# 08-STM32-01.net
KiCad netlist of a schematic drawn in Altium Designer
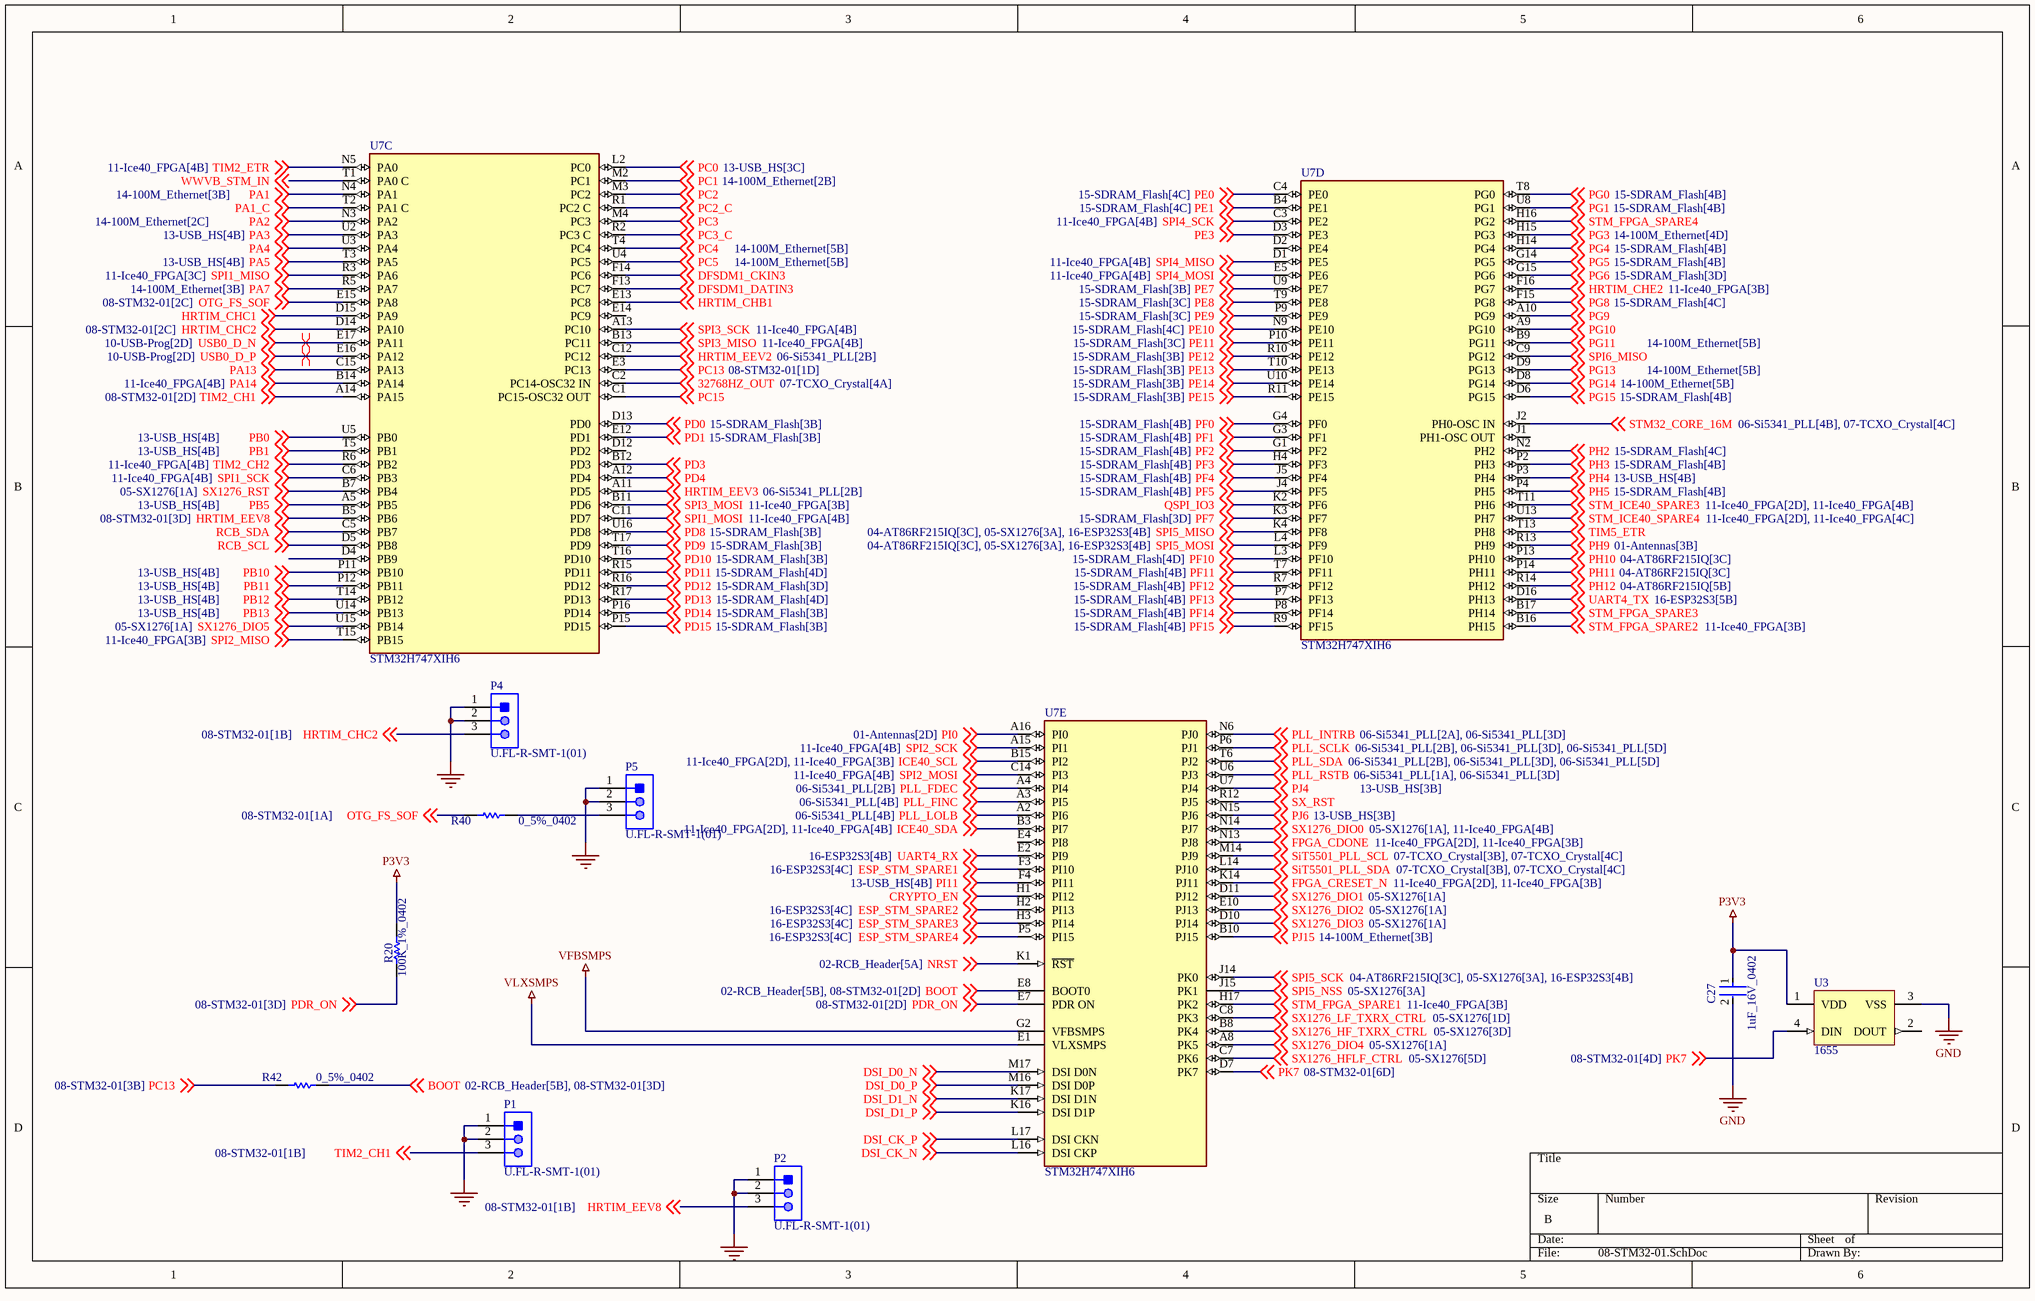
[diagram p0: 08-STM32-01.SchDoc]

(export (version "E")
  (design (tool "Eeschema 10.0.6"))
  (components
    (comp (ref "C27")
      (value "1uF_16V_0402")
      (footprint "FP-0402-L_1_0_0_05-W_0_5-IPC_A")
      (description "None")
      (fields (field (name "TOLERANCE") "10%"))
      (libsource (lib "Altium Content Vault") (part "b4654b650e69147ec39a6b967a45e02"))
    )
    (comp (ref "P1")
      (value "U.FL-R-SMT-1(01)")
      (footprint "HRS-U.FL-R-SMT-3_V")
      (description "Ultra Small Coaxial Connector, 6 GHz, -40 to 90 degC, 3-Pin SMD, RoHS, Bulk")
      (fields (field (name "MANUFACTURER") "Hirose Electric"))
      (libsource (lib "Altium Content Vault") (part "CN-1P-M-R3"))
    )
    (comp (ref "P2")
      (value "U.FL-R-SMT-1(01)")
      (footprint "HRS-U.FL-R-SMT-3_V")
      (description "Ultra Small Coaxial Connector, 6 GHz, -40 to 90 degC, 3-Pin SMD, RoHS, Bulk")
      (fields (field (name "MANUFACTURER") "Hirose Electric"))
      (libsource (lib "Altium Content Vault") (part "CN-1P-M-R3"))
    )
    (comp (ref "P4")
      (value "U.FL-R-SMT-1(01)")
      (footprint "HRS-U.FL-R-SMT-3_V")
      (description "Ultra Small Coaxial Connector, 6 GHz, -40 to 90 degC, 3-Pin SMD, RoHS, Bulk")
      (fields (field (name "MANUFACTURER") "Hirose Electric"))
      (libsource (lib "Altium Content Vault") (part "CN-1P-M-R3"))
    )
    (comp (ref "P5")
      (value "U.FL-R-SMT-1(01)")
      (footprint "HRS-U.FL-R-SMT-3_V")
      (description "Ultra Small Coaxial Connector, 6 GHz, -40 to 90 degC, 3-Pin SMD, RoHS, Bulk")
      (fields (field (name "MANUFACTURER") "Hirose Electric"))
      (libsource (lib "Altium Content Vault") (part "CN-1P-M-R3"))
    )
    (comp (ref "R20")
      (value "100K_1%_0402")
      (footprint "RESC1005X40X25ML05T10")
      (fields (field (name "MANUFACTURER") "Yageo") (field (name "PART NUMBER") "RC0402FR-13100KL"))
      (libsource (lib "Altium Content Vault") (part "RES"))
    )
    (comp (ref "R40")
      (value "0_5%_0402")
      (footprint "RESC1005X40X25NL05T10")
      (fields (field (name "MANUFACTURER") "Panasonic") (field (name "PART NUMBER") "ERJ-U020R00X"))
      (libsource (lib "Altium Content Vault") (part "RES"))
    )
    (comp (ref "R42")
      (value "0_5%_0402")
      (footprint "RESC1005X40X25NL05T10")
      (fields (field (name "MANUFACTURER") "Panasonic") (field (name "PART NUMBER") "ERJ-U020R00X"))
      (libsource (lib "Altium Content Vault") (part "RES"))
    )
    (comp (ref "U3")
      (value "1655")
      (footprint "ADA-RGB-1655_V")
      (fields (field (name "MANUFACTURER") "Adafruit-Industries-LLC"))
      (libsource (lib "Altium Content Vault") (part "ADA-RGB-1655-4"))
    )
    (comp (ref "U7")
      (value "STM32H747XIH6")
      (footprint "FP-TFBGA240+25-A07U-MFG")
      (description "HIGH-PERFORMANCE AND DSP WITH DP")
      (fields
        (field (name "MANUFACTURER") "STMicroelectronics")
        (field (name "OCTOPART") "https://octopart.com/stm32h747xih6-stmicroelectronics-100293943")
      )
      (libsource (lib "Altium Content Vault") (part "41f839bdfd00d9510c8672f0f410bfb"))
    )
  )
  (nets
    (net (code "1") (name "32768HZ_OUT") (class "Default")
      (node (ref "U7") (pin "C2") (pinfunction "PC14-OSC32_IN_C2") (pintype "bidirectional"))
    )
    (net (code "2") (name "BOOT") (class "Default")
      (node (ref "R42") (pin "2") (pinfunction "2_2") (pintype "passive"))
      (node (ref "U7") (pin "E8") (pinfunction "BOOT0_E8") (pintype "passive"))
    )
    (net (code "3") (name "CRYPTO_EN") (class "Default")
      (node (ref "U7") (pin "H1") (pinfunction "PI12_H1") (pintype "bidirectional"))
    )
    (net (code "4") (name "DFSDM1_CKIN3") (class "Default")
      (node (ref "U7") (pin "F14") (pinfunction "PC6_F14") (pintype "bidirectional"))
    )
    (net (code "5") (name "DFSDM1_DATIN3") (class "Default")
      (node (ref "U7") (pin "F13") (pinfunction "PC7_F13") (pintype "bidirectional"))
    )
    (net (code "6") (name "DSI_CK_N") (class "Default")
      (node (ref "U7") (pin "L16") (pinfunction "DSI_CKP_L16") (pintype "input"))
    )
    (net (code "7") (name "DSI_CK_P") (class "Default")
      (node (ref "U7") (pin "L17") (pinfunction "DSI_CKN_L17") (pintype "input"))
    )
    (net (code "8") (name "DSI_D0_N") (class "Default")
      (node (ref "U7") (pin "M17") (pinfunction "DSI_D0N_M17") (pintype "input"))
    )
    (net (code "9") (name "DSI_D0_P") (class "Default")
      (node (ref "U7") (pin "M16") (pinfunction "DSI_D0P_M16") (pintype "input"))
    )
    (net (code "10") (name "DSI_D1_N") (class "Default")
      (node (ref "U7") (pin "K17") (pinfunction "DSI_D1N_K17") (pintype "input"))
    )
    (net (code "11") (name "DSI_D1_P") (class "Default")
      (node (ref "U7") (pin "K16") (pinfunction "DSI_D1P_K16") (pintype "input"))
    )
    (net (code "12") (name "ESP_STM_SPARE1") (class "Default")
      (node (ref "U7") (pin "F3") (pinfunction "PI10_F3") (pintype "bidirectional"))
    )
    (net (code "13") (name "ESP_STM_SPARE2") (class "Default")
      (node (ref "U7") (pin "H2") (pinfunction "PI13_H2") (pintype "bidirectional"))
    )
    (net (code "14") (name "ESP_STM_SPARE3") (class "Default")
      (node (ref "U7") (pin "H3") (pinfunction "PI14_H3") (pintype "bidirectional"))
    )
    (net (code "15") (name "ESP_STM_SPARE4") (class "Default")
      (node (ref "U7") (pin "P5") (pinfunction "PI15_P5") (pintype "bidirectional"))
    )
    (net (code "16") (name "FPGA_CDONE") (class "Default")
      (node (ref "U7") (pin "N13") (pinfunction "PJ8_N13") (pintype "bidirectional"))
    )
    (net (code "17") (name "FPGA_CRESET_N") (class "Default")
      (node (ref "U7") (pin "K14") (pinfunction "PJ11_K14") (pintype "bidirectional"))
    )
    (net (code "18") (name "GND") (class "Default")
      (node (ref "C27") (pin "2") (pinfunction "2_2") (pintype "passive"))
      (node (ref "P1") (pin "1") (pinfunction "1_1") (pintype "passive"))
      (node (ref "P1") (pin "2") (pinfunction "2_2") (pintype "passive"))
      (node (ref "P2") (pin "1") (pinfunction "1_1") (pintype "passive"))
      (node (ref "P2") (pin "2") (pinfunction "2_2") (pintype "passive"))
      (node (ref "P4") (pin "1") (pinfunction "1_1") (pintype "passive"))
      (node (ref "P4") (pin "2") (pinfunction "2_2") (pintype "passive"))
      (node (ref "P5") (pin "1") (pinfunction "1_1") (pintype "passive"))
      (node (ref "P5") (pin "2") (pinfunction "2_2") (pintype "passive"))
      (node (ref "U3") (pin "3") (pinfunction "VSS_3") (pintype "power_in"))
    )
    (net (code "19") (name "HRTIM_CHB1") (class "Default")
      (node (ref "U7") (pin "E13") (pinfunction "PC8_E13") (pintype "bidirectional"))
    )
    (net (code "20") (name "HRTIM_CHC1") (class "Default")
      (node (ref "U7") (pin "D15") (pinfunction "PA9_D15") (pintype "bidirectional"))
    )
    (net (code "21") (name "HRTIM_CHC2") (class "Default")
      (node (ref "P4") (pin "3") (pinfunction "3_3") (pintype "passive"))
      (node (ref "U7") (pin "D14") (pinfunction "PA10_D14") (pintype "bidirectional"))
    )
    (net (code "22") (name "HRTIM_CHE2") (class "Default")
      (node (ref "U7") (pin "F16") (pinfunction "PG7_F16") (pintype "bidirectional"))
    )
    (net (code "23") (name "HRTIM_EEV2") (class "Default")
      (node (ref "U7") (pin "C12") (pinfunction "PC12_C12") (pintype "bidirectional"))
    )
    (net (code "24") (name "HRTIM_EEV3") (class "Default")
      (node (ref "U7") (pin "A11") (pinfunction "PD5_A11") (pintype "bidirectional"))
    )
    (net (code "25") (name "HRTIM_EEV8") (class "Default")
      (node (ref "P2") (pin "3") (pinfunction "3_3") (pintype "passive"))
      (node (ref "U7") (pin "B5") (pinfunction "PB6_B5") (pintype "bidirectional"))
    )
    (net (code "26") (name "ICE40_SCL") (class "Default")
      (node (ref "U7") (pin "B15") (pinfunction "PI2_B15") (pintype "bidirectional"))
    )
    (net (code "27") (name "ICE40_SDA") (class "Default")
      (node (ref "U7") (pin "B3") (pinfunction "PI7_B3") (pintype "bidirectional"))
    )
    (net (code "28") (name "NRST") (class "Default")
      (node (ref "U7") (pin "K1") (pinfunction "~{RST}_K1") (pintype "input"))
    )
    (net (code "29") (name "Net-(P5-Pad3)") (class "Default")
      (node (ref "P5") (pin "3") (pinfunction "3_3") (pintype "passive"))
      (node (ref "R40") (pin "2") (pinfunction "2_2") (pintype "passive"))
    )
    (net (code "30") (name "OTG_FS_SOF") (class "Default")
      (node (ref "R40") (pin "1") (pinfunction "1_1") (pintype "passive"))
      (node (ref "U7") (pin "E15") (pinfunction "PA8_E15") (pintype "bidirectional"))
    )
    (net (code "31") (name "P3V3") (class "Default")
      (node (ref "C27") (pin "1") (pinfunction "1_1") (pintype "passive"))
      (node (ref "R20") (pin "2") (pinfunction "2_2") (pintype "passive"))
      (node (ref "U3") (pin "1") (pinfunction "VDD_1") (pintype "power_in"))
    )
    (net (code "32") (name "PA1") (class "Default")
      (node (ref "U7") (pin "N4") (pinfunction "PA1_N4") (pintype "bidirectional"))
    )
    (net (code "33") (name "PA1_C") (class "Default")
      (node (ref "U7") (pin "T2") (pinfunction "PA1_C_T2") (pintype "bidirectional"))
    )
    (net (code "34") (name "PA2") (class "Default")
      (node (ref "U7") (pin "N3") (pinfunction "PA2_N3") (pintype "bidirectional"))
    )
    (net (code "35") (name "PA3") (class "Default")
      (node (ref "U7") (pin "U2") (pinfunction "PA3_U2") (pintype "bidirectional"))
    )
    (net (code "36") (name "PA4") (class "Default")
      (node (ref "U7") (pin "U3") (pinfunction "PA4_U3") (pintype "bidirectional"))
    )
    (net (code "37") (name "PA5") (class "Default")
      (node (ref "U7") (pin "T3") (pinfunction "PA5_T3") (pintype "bidirectional"))
    )
    (net (code "38") (name "PA7") (class "Default")
      (node (ref "U7") (pin "R5") (pinfunction "PA7_R5") (pintype "bidirectional"))
    )
    (net (code "39") (name "PA13") (class "Default")
      (node (ref "U7") (pin "C15") (pinfunction "PA13_C15") (pintype "bidirectional"))
    )
    (net (code "40") (name "PA14") (class "Default")
      (node (ref "U7") (pin "B14") (pinfunction "PA14_B14") (pintype "bidirectional"))
    )
    (net (code "41") (name "PB0") (class "Default")
      (node (ref "U7") (pin "U5") (pinfunction "PB0_U5") (pintype "bidirectional"))
    )
    (net (code "42") (name "PB1") (class "Default")
      (node (ref "U7") (pin "T5") (pinfunction "PB1_T5") (pintype "bidirectional"))
    )
    (net (code "43") (name "PB5") (class "Default")
      (node (ref "U7") (pin "A5") (pinfunction "PB5_A5") (pintype "bidirectional"))
    )
    (net (code "44") (name "PB10") (class "Default")
      (node (ref "U7") (pin "P11") (pinfunction "PB10_P11") (pintype "bidirectional"))
    )
    (net (code "45") (name "PB11") (class "Default")
      (node (ref "U7") (pin "P12") (pinfunction "PB11_P12") (pintype "bidirectional"))
    )
    (net (code "46") (name "PB12") (class "Default")
      (node (ref "U7") (pin "T14") (pinfunction "PB12_T14") (pintype "bidirectional"))
    )
    (net (code "47") (name "PB13") (class "Default")
      (node (ref "U7") (pin "U14") (pinfunction "PB13_U14") (pintype "bidirectional"))
    )
    (net (code "48") (name "PC0") (class "Default")
      (node (ref "U7") (pin "L2") (pinfunction "PC0_L2") (pintype "bidirectional"))
    )
    (net (code "49") (name "PC1") (class "Default")
      (node (ref "U7") (pin "M2") (pinfunction "PC1_M2") (pintype "bidirectional"))
    )
    (net (code "50") (name "PC2") (class "Default")
      (node (ref "U7") (pin "M3") (pinfunction "PC2_M3") (pintype "bidirectional"))
    )
    (net (code "51") (name "PC2_C") (class "Default")
      (node (ref "U7") (pin "R1") (pinfunction "PC2_C_R1") (pintype "bidirectional"))
    )
    (net (code "52") (name "PC3") (class "Default")
      (node (ref "U7") (pin "M4") (pinfunction "PC3_M4") (pintype "bidirectional"))
    )
    (net (code "53") (name "PC3_C") (class "Default")
      (node (ref "U7") (pin "R2") (pinfunction "PC3_C_R2") (pintype "bidirectional"))
    )
    (net (code "54") (name "PC4") (class "Default")
      (node (ref "U7") (pin "T4") (pinfunction "PC4_T4") (pintype "bidirectional"))
    )
    (net (code "55") (name "PC5") (class "Default")
      (node (ref "U7") (pin "U4") (pinfunction "PC5_U4") (pintype "bidirectional"))
    )
    (net (code "56") (name "PC13") (class "Default")
      (node (ref "R42") (pin "1") (pinfunction "1_1") (pintype "passive"))
      (node (ref "U7") (pin "E3") (pinfunction "PC13_E3") (pintype "bidirectional"))
    )
    (net (code "57") (name "PC15") (class "Default")
      (node (ref "U7") (pin "C1") (pinfunction "PC15-OSC32_OUT_C1") (pintype "bidirectional"))
    )
    (net (code "58") (name "PD0") (class "Default")
      (node (ref "U7") (pin "D13") (pinfunction "PD0_D13") (pintype "bidirectional"))
    )
    (net (code "59") (name "PD1") (class "Default")
      (node (ref "U7") (pin "E12") (pinfunction "PD1_E12") (pintype "bidirectional"))
    )
    (net (code "60") (name "PD3") (class "Default")
      (node (ref "U7") (pin "B12") (pinfunction "PD3_B12") (pintype "bidirectional"))
    )
    (net (code "61") (name "PD4") (class "Default")
      (node (ref "U7") (pin "A12") (pinfunction "PD4_A12") (pintype "bidirectional"))
    )
    (net (code "62") (name "PD8") (class "Default")
      (node (ref "U7") (pin "U16") (pinfunction "PD8_U16") (pintype "bidirectional"))
    )
    (net (code "63") (name "PD9") (class "Default")
      (node (ref "U7") (pin "T17") (pinfunction "PD9_T17") (pintype "bidirectional"))
    )
    (net (code "64") (name "PD10") (class "Default")
      (node (ref "U7") (pin "T16") (pinfunction "PD10_T16") (pintype "bidirectional"))
    )
    (net (code "65") (name "PD11") (class "Default")
      (node (ref "U7") (pin "R15") (pinfunction "PD11_R15") (pintype "bidirectional"))
    )
    (net (code "66") (name "PD12") (class "Default")
      (node (ref "U7") (pin "R16") (pinfunction "PD12_R16") (pintype "bidirectional"))
    )
    (net (code "67") (name "PD13") (class "Default")
      (node (ref "U7") (pin "R17") (pinfunction "PD13_R17") (pintype "bidirectional"))
    )
    (net (code "68") (name "PD14") (class "Default")
      (node (ref "U7") (pin "P16") (pinfunction "PD14_P16") (pintype "bidirectional"))
    )
    (net (code "69") (name "PD15") (class "Default")
      (node (ref "U7") (pin "P15") (pinfunction "PD15_P15") (pintype "bidirectional"))
    )
    (net (code "70") (name "PDR_ON") (class "Default")
      (node (ref "R20") (pin "1") (pinfunction "1_1") (pintype "passive"))
      (node (ref "U7") (pin "E7") (pinfunction "PDR_ON_E7") (pintype "power_in"))
    )
    (net (code "71") (name "PE0") (class "Default")
      (node (ref "U7") (pin "C4") (pinfunction "PE0_C4") (pintype "bidirectional"))
    )
    (net (code "72") (name "PE1") (class "Default")
      (node (ref "U7") (pin "B4") (pinfunction "PE1_B4") (pintype "bidirectional"))
    )
    (net (code "73") (name "PE3") (class "Default")
      (node (ref "U7") (pin "D3") (pinfunction "PE3_D3") (pintype "bidirectional"))
    )
    (net (code "74") (name "PE7") (class "Default")
      (node (ref "U7") (pin "U9") (pinfunction "PE7_U9") (pintype "bidirectional"))
    )
    (net (code "75") (name "PE8") (class "Default")
      (node (ref "U7") (pin "T9") (pinfunction "PE8_T9") (pintype "bidirectional"))
    )
    (net (code "76") (name "PE9") (class "Default")
      (node (ref "U7") (pin "P9") (pinfunction "PE9_P9") (pintype "bidirectional"))
    )
    (net (code "77") (name "PE10") (class "Default")
      (node (ref "U7") (pin "N9") (pinfunction "PE10_N9") (pintype "bidirectional"))
    )
    (net (code "78") (name "PE11") (class "Default")
      (node (ref "U7") (pin "P10") (pinfunction "PE11_P10") (pintype "bidirectional"))
    )
    (net (code "79") (name "PE12") (class "Default")
      (node (ref "U7") (pin "R10") (pinfunction "PE12_R10") (pintype "bidirectional"))
    )
    (net (code "80") (name "PE13") (class "Default")
      (node (ref "U7") (pin "T10") (pinfunction "PE13_T10") (pintype "bidirectional"))
    )
    (net (code "81") (name "PE14") (class "Default")
      (node (ref "U7") (pin "U10") (pinfunction "PE14_U10") (pintype "bidirectional"))
    )
    (net (code "82") (name "PE15") (class "Default")
      (node (ref "U7") (pin "R11") (pinfunction "PE15_R11") (pintype "bidirectional"))
    )
    (net (code "83") (name "PF0") (class "Default")
      (node (ref "U7") (pin "G4") (pinfunction "PF0_G4") (pintype "bidirectional"))
    )
    (net (code "84") (name "PF1") (class "Default")
      (node (ref "U7") (pin "G3") (pinfunction "PF1_G3") (pintype "bidirectional"))
    )
    (net (code "85") (name "PF2") (class "Default")
      (node (ref "U7") (pin "G1") (pinfunction "PF2_G1") (pintype "bidirectional"))
    )
    (net (code "86") (name "PF3") (class "Default")
      (node (ref "U7") (pin "H4") (pinfunction "PF3_H4") (pintype "bidirectional"))
    )
    (net (code "87") (name "PF4") (class "Default")
      (node (ref "U7") (pin "J5") (pinfunction "PF4_J5") (pintype "bidirectional"))
    )
    (net (code "88") (name "PF5") (class "Default")
      (node (ref "U7") (pin "J4") (pinfunction "PF5_J4") (pintype "bidirectional"))
    )
    (net (code "89") (name "PF7") (class "Default")
      (node (ref "U7") (pin "K3") (pinfunction "PF7_K3") (pintype "bidirectional"))
    )
    (net (code "90") (name "PF10") (class "Default")
      (node (ref "U7") (pin "L3") (pinfunction "PF10_L3") (pintype "bidirectional"))
    )
    (net (code "91") (name "PF11") (class "Default")
      (node (ref "U7") (pin "T7") (pinfunction "PF11_T7") (pintype "bidirectional"))
    )
    (net (code "92") (name "PF12") (class "Default")
      (node (ref "U7") (pin "R7") (pinfunction "PF12_R7") (pintype "bidirectional"))
    )
    (net (code "93") (name "PF13") (class "Default")
      (node (ref "U7") (pin "P7") (pinfunction "PF13_P7") (pintype "bidirectional"))
    )
    (net (code "94") (name "PF14") (class "Default")
      (node (ref "U7") (pin "P8") (pinfunction "PF14_P8") (pintype "bidirectional"))
    )
    (net (code "95") (name "PF15") (class "Default")
      (node (ref "U7") (pin "R9") (pinfunction "PF15_R9") (pintype "bidirectional"))
    )
    (net (code "96") (name "PG0") (class "Default")
      (node (ref "U7") (pin "T8") (pinfunction "PG0_T8") (pintype "bidirectional"))
    )
    (net (code "97") (name "PG1") (class "Default")
      (node (ref "U7") (pin "U8") (pinfunction "PG1_U8") (pintype "bidirectional"))
    )
    (net (code "98") (name "PG3") (class "Default")
      (node (ref "U7") (pin "H15") (pinfunction "PG3_H15") (pintype "bidirectional"))
    )
    (net (code "99") (name "PG4") (class "Default")
      (node (ref "U7") (pin "H14") (pinfunction "PG4_H14") (pintype "bidirectional"))
    )
    (net (code "100") (name "PG5") (class "Default")
      (node (ref "U7") (pin "G14") (pinfunction "PG5_G14") (pintype "bidirectional"))
    )
    (net (code "101") (name "PG6") (class "Default")
      (node (ref "U7") (pin "G15") (pinfunction "PG6_G15") (pintype "bidirectional"))
    )
    (net (code "102") (name "PG8") (class "Default")
      (node (ref "U7") (pin "F15") (pinfunction "PG8_F15") (pintype "bidirectional"))
    )
    (net (code "103") (name "PG9") (class "Default")
      (node (ref "U7") (pin "A10") (pinfunction "PG9_A10") (pintype "bidirectional"))
    )
    (net (code "104") (name "PG10") (class "Default")
      (node (ref "U7") (pin "A9") (pinfunction "PG10_A9") (pintype "bidirectional"))
    )
    (net (code "105") (name "PG11") (class "Default")
      (node (ref "U7") (pin "B9") (pinfunction "PG11_B9") (pintype "bidirectional"))
    )
    (net (code "106") (name "PG13") (class "Default")
      (node (ref "U7") (pin "D9") (pinfunction "PG13_D9") (pintype "bidirectional"))
    )
    (net (code "107") (name "PG14") (class "Default")
      (node (ref "U7") (pin "D8") (pinfunction "PG14_D8") (pintype "bidirectional"))
    )
    (net (code "108") (name "PG15") (class "Default")
      (node (ref "U7") (pin "D6") (pinfunction "PG15_D6") (pintype "bidirectional"))
    )
    (net (code "109") (name "PH2") (class "Default")
      (node (ref "U7") (pin "N2") (pinfunction "PH2_N2") (pintype "bidirectional"))
    )
    (net (code "110") (name "PH3") (class "Default")
      (node (ref "U7") (pin "P2") (pinfunction "PH3_P2") (pintype "bidirectional"))
    )
    (net (code "111") (name "PH4") (class "Default")
      (node (ref "U7") (pin "P3") (pinfunction "PH4_P3") (pintype "bidirectional"))
    )
    (net (code "112") (name "PH5") (class "Default")
      (node (ref "U7") (pin "P4") (pinfunction "PH5_P4") (pintype "bidirectional"))
    )
    (net (code "113") (name "PH9") (class "Default")
      (node (ref "U7") (pin "R13") (pinfunction "PH9_R13") (pintype "bidirectional"))
    )
    (net (code "114") (name "PH10") (class "Default")
      (node (ref "U7") (pin "P13") (pinfunction "PH10_P13") (pintype "bidirectional"))
    )
    (net (code "115") (name "PH11") (class "Default")
      (node (ref "U7") (pin "P14") (pinfunction "PH11_P14") (pintype "bidirectional"))
    )
    (net (code "116") (name "PH12") (class "Default")
      (node (ref "U7") (pin "R14") (pinfunction "PH12_R14") (pintype "bidirectional"))
    )
    (net (code "117") (name "PI0") (class "Default")
      (node (ref "U7") (pin "A16") (pinfunction "PI0_A16") (pintype "bidirectional"))
    )
    (net (code "118") (name "PI11") (class "Default")
      (node (ref "U7") (pin "F4") (pinfunction "PI11_F4") (pintype "bidirectional"))
    )
    (net (code "119") (name "PJ4") (class "Default")
      (node (ref "U7") (pin "U7") (pinfunction "PJ4_U7") (pintype "bidirectional"))
    )
    (net (code "120") (name "PJ6") (class "Default")
      (node (ref "U7") (pin "N15") (pinfunction "PJ6_N15") (pintype "bidirectional"))
    )
    (net (code "121") (name "PJ15") (class "Default")
      (node (ref "U7") (pin "B10") (pinfunction "PJ15_B10") (pintype "bidirectional"))
    )
    (net (code "122") (name "PK7") (class "Default")
      (node (ref "U3") (pin "4") (pinfunction "DIN_4") (pintype "input"))
      (node (ref "U7") (pin "D7") (pinfunction "PK7_D7") (pintype "bidirectional"))
    )
    (net (code "123") (name "PLL_FDEC") (class "Default")
      (node (ref "U7") (pin "A4") (pinfunction "PI4_A4") (pintype "bidirectional"))
    )
    (net (code "124") (name "PLL_FINC") (class "Default")
      (node (ref "U7") (pin "A3") (pinfunction "PI5_A3") (pintype "bidirectional"))
    )
    (net (code "125") (name "PLL_INTRB") (class "Default")
      (node (ref "U7") (pin "N6") (pinfunction "PJ0_N6") (pintype "bidirectional"))
    )
    (net (code "126") (name "PLL_LOLB") (class "Default")
      (node (ref "U7") (pin "A2") (pinfunction "PI6_A2") (pintype "bidirectional"))
    )
    (net (code "127") (name "PLL_RSTB") (class "Default")
      (node (ref "U7") (pin "U6") (pinfunction "PJ3_U6") (pintype "bidirectional"))
    )
    (net (code "128") (name "PLL_SCLK") (class "Default")
      (node (ref "U7") (pin "P6") (pinfunction "PJ1_P6") (pintype "bidirectional"))
    )
    (net (code "129") (name "PLL_SDA") (class "Default")
      (node (ref "U7") (pin "T6") (pinfunction "PJ2_T6") (pintype "bidirectional"))
    )
    (net (code "130") (name "QSPI_IO3") (class "Default")
      (node (ref "U7") (pin "K2") (pinfunction "PF6_K2") (pintype "bidirectional"))
    )
    (net (code "131") (name "RCB_SCL") (class "Default")
      (node (ref "U7") (pin "D5") (pinfunction "PB8_D5") (pintype "bidirectional"))
    )
    (net (code "132") (name "RCB_SDA") (class "Default")
      (node (ref "U7") (pin "C5") (pinfunction "PB7_C5") (pintype "bidirectional"))
    )
    (net (code "133") (name "SPI1_MISO") (class "Default")
      (node (ref "U7") (pin "R3") (pinfunction "PA6_R3") (pintype "bidirectional"))
    )
    (net (code "134") (name "SPI1_MOSI") (class "Default")
      (node (ref "U7") (pin "C11") (pinfunction "PD7_C11") (pintype "bidirectional"))
    )
    (net (code "135") (name "SPI1_SCK") (class "Default")
      (node (ref "U7") (pin "C6") (pinfunction "PB3_C6") (pintype "bidirectional"))
    )
    (net (code "136") (name "SPI2_MISO") (class "Default")
      (node (ref "U7") (pin "T15") (pinfunction "PB15_T15") (pintype "bidirectional"))
    )
    (net (code "137") (name "SPI2_MOSI") (class "Default")
      (node (ref "U7") (pin "C14") (pinfunction "PI3_C14") (pintype "bidirectional"))
    )
    (net (code "138") (name "SPI2_SCK") (class "Default")
      (node (ref "U7") (pin "A15") (pinfunction "PI1_A15") (pintype "bidirectional"))
    )
    (net (code "139") (name "SPI3_MISO") (class "Default")
      (node (ref "U7") (pin "B13") (pinfunction "PC11_B13") (pintype "bidirectional"))
    )
    (net (code "140") (name "SPI3_MOSI") (class "Default")
      (node (ref "U7") (pin "B11") (pinfunction "PD6_B11") (pintype "bidirectional"))
    )
    (net (code "141") (name "SPI3_SCK") (class "Default")
      (node (ref "U7") (pin "A13") (pinfunction "PC10_A13") (pintype "bidirectional"))
    )
    (net (code "142") (name "SPI4_MISO") (class "Default")
      (node (ref "U7") (pin "D1") (pinfunction "PE5_D1") (pintype "bidirectional"))
    )
    (net (code "143") (name "SPI4_MOSI") (class "Default")
      (node (ref "U7") (pin "E5") (pinfunction "PE6_E5") (pintype "bidirectional"))
    )
    (net (code "144") (name "SPI4_SCK") (class "Default")
      (node (ref "U7") (pin "C3") (pinfunction "PE2_C3") (pintype "bidirectional"))
    )
    (net (code "145") (name "SPI5_MISO") (class "Default")
      (node (ref "U7") (pin "K4") (pinfunction "PF8_K4") (pintype "bidirectional"))
    )
    (net (code "146") (name "SPI5_MOSI") (class "Default")
      (node (ref "U7") (pin "L4") (pinfunction "PF9_L4") (pintype "bidirectional"))
    )
    (net (code "147") (name "SPI5_NSS") (class "Default")
      (node (ref "U7") (pin "J15") (pinfunction "PK1_J15") (pintype "passive"))
    )
    (net (code "148") (name "SPI5_SCK") (class "Default")
      (node (ref "U7") (pin "J14") (pinfunction "PK0_J14") (pintype "bidirectional"))
    )
    (net (code "149") (name "SPI6_MISO") (class "Default")
      (node (ref "U7") (pin "C9") (pinfunction "PG12_C9") (pintype "bidirectional"))
    )
    (net (code "150") (name "STM32_CORE_16M") (class "Default")
      (node (ref "U7") (pin "J2") (pinfunction "PH0-OSC_IN_J2") (pintype "bidirectional"))
    )
    (net (code "151") (name "STM_FPGA_SPARE1") (class "Default")
      (node (ref "U7") (pin "H17") (pinfunction "PK2_H17") (pintype "bidirectional"))
    )
    (net (code "152") (name "STM_FPGA_SPARE2") (class "Default")
      (node (ref "U7") (pin "B16") (pinfunction "PH15_B16") (pintype "bidirectional"))
    )
    (net (code "153") (name "STM_FPGA_SPARE3") (class "Default")
      (node (ref "U7") (pin "B17") (pinfunction "PH14_B17") (pintype "bidirectional"))
    )
    (net (code "154") (name "STM_FPGA_SPARE4") (class "Default")
      (node (ref "U7") (pin "H16") (pinfunction "PG2_H16") (pintype "bidirectional"))
    )
    (net (code "155") (name "STM_ICE40_SPARE3") (class "Default")
      (node (ref "U7") (pin "T11") (pinfunction "PH6_T11") (pintype "bidirectional"))
    )
    (net (code "156") (name "STM_ICE40_SPARE4") (class "Default")
      (node (ref "U7") (pin "U13") (pinfunction "PH7_U13") (pintype "bidirectional"))
    )
    (net (code "157") (name "SX1276_DIO0") (class "Default")
      (node (ref "U7") (pin "N14") (pinfunction "PJ7_N14") (pintype "bidirectional"))
    )
    (net (code "158") (name "SX1276_DIO1") (class "Default")
      (node (ref "U7") (pin "D11") (pinfunction "PJ12_D11") (pintype "bidirectional"))
    )
    (net (code "159") (name "SX1276_DIO2") (class "Default")
      (node (ref "U7") (pin "E10") (pinfunction "PJ13_E10") (pintype "bidirectional"))
    )
    (net (code "160") (name "SX1276_DIO3") (class "Default")
      (node (ref "U7") (pin "D10") (pinfunction "PJ14_D10") (pintype "bidirectional"))
    )
    (net (code "161") (name "SX1276_DIO4") (class "Default")
      (node (ref "U7") (pin "A8") (pinfunction "PK5_A8") (pintype "bidirectional"))
    )
    (net (code "162") (name "SX1276_DIO5") (class "Default")
      (node (ref "U7") (pin "U15") (pinfunction "PB14_U15") (pintype "bidirectional"))
    )
    (net (code "163") (name "SX1276_HFLF_CTRL") (class "Default")
      (node (ref "U7") (pin "C7") (pinfunction "PK6_C7") (pintype "bidirectional"))
    )
    (net (code "164") (name "SX1276_HF_TXRX_CTRL") (class "Default")
      (node (ref "U7") (pin "B8") (pinfunction "PK4_B8") (pintype "bidirectional"))
    )
    (net (code "165") (name "SX1276_LF_TXRX_CTRL") (class "Default")
      (node (ref "U7") (pin "C8") (pinfunction "PK3_C8") (pintype "bidirectional"))
    )
    (net (code "166") (name "SX1276_RST") (class "Default")
      (node (ref "U7") (pin "B7") (pinfunction "PB4_B7") (pintype "bidirectional"))
    )
    (net (code "167") (name "SX_RST") (class "Default")
      (node (ref "U7") (pin "R12") (pinfunction "PJ5_R12") (pintype "bidirectional"))
    )
    (net (code "168") (name "SiT5501_PLL_SCL") (class "Default")
      (node (ref "U7") (pin "M14") (pinfunction "PJ9_M14") (pintype "bidirectional"))
    )
    (net (code "169") (name "SiT5501_PLL_SDA") (class "Default")
      (node (ref "U7") (pin "L14") (pinfunction "PJ10_L14") (pintype "bidirectional"))
    )
    (net (code "170") (name "TIM2_CH1") (class "Default")
      (node (ref "P1") (pin "3") (pinfunction "3_3") (pintype "passive"))
      (node (ref "U7") (pin "A14") (pinfunction "PA15_A14") (pintype "bidirectional"))
    )
    (net (code "171") (name "TIM2_CH2") (class "Default")
      (node (ref "U7") (pin "R6") (pinfunction "PB2_R6") (pintype "bidirectional"))
    )
    (net (code "172") (name "TIM2_ETR") (class "Default")
      (node (ref "U7") (pin "N5") (pinfunction "PA0_N5") (pintype "bidirectional"))
    )
    (net (code "173") (name "TIM5_ETR") (class "Default")
      (node (ref "U7") (pin "T13") (pinfunction "PH8_T13") (pintype "bidirectional"))
    )
    (net (code "174") (name "UART4_RX") (class "Default")
      (node (ref "U7") (pin "E2") (pinfunction "PI9_E2") (pintype "bidirectional"))
    )
    (net (code "175") (name "UART4_TX") (class "Default")
      (node (ref "U7") (pin "D16") (pinfunction "PH13_D16") (pintype "bidirectional"))
    )
    (net (code "176") (name "USB0_D_N") (class "Default")
      (node (ref "U7") (pin "E17") (pinfunction "PA11_E17") (pintype "bidirectional"))
    )
    (net (code "177") (name "USB0_D_P") (class "Default")
      (node (ref "U7") (pin "E16") (pinfunction "PA12_E16") (pintype "bidirectional"))
    )
    (net (code "178") (name "VFBSMPS") (class "Default")
      (node (ref "U7") (pin "G2") (pinfunction "VFBSMPS_G2") (pintype "power_in"))
    )
    (net (code "179") (name "VLXSMPS") (class "Default")
      (node (ref "U7") (pin "E1") (pinfunction "VLXSMPS_E1") (pintype "power_in"))
    )
    (net (code "180") (name "WWVB_STM_IN") (class "Default")
      (node (ref "U7") (pin "T1") (pinfunction "PA0_C_T1") (pintype "bidirectional"))
    )
    (net (code "181") (name "unconnected-(U3-DOUT-Pad2)") (class "Default")
      (node (ref "U3") (pin "2") (pinfunction "DOUT_2") (pintype "output"))
    )
    (net (code "182") (name "unconnected-(U7C-PB9-PadD4)") (class "Default")
      (node (ref "U7") (pin "D4") (pinfunction "PB9_D4") (pintype "bidirectional"))
    )
    (net (code "183") (name "unconnected-(U7C-PC9-PadE14)") (class "Default")
      (node (ref "U7") (pin "E14") (pinfunction "PC9_E14") (pintype "bidirectional"))
    )
    (net (code "184") (name "unconnected-(U7C-PD2-PadD12)") (class "Default")
      (node (ref "U7") (pin "D12") (pinfunction "PD2_D12") (pintype "bidirectional"))
    )
    (net (code "185") (name "unconnected-(U7D-PE4-PadD2)") (class "Default")
      (node (ref "U7") (pin "D2") (pinfunction "PE4_D2") (pintype "bidirectional"))
    )
    (net (code "186") (name "unconnected-(U7D-PH1-OSC_OUT-PadJ1)") (class "Default")
      (node (ref "U7") (pin "J1") (pinfunction "PH1-OSC_OUT_J1") (pintype "bidirectional"))
    )
    (net (code "187") (name "unconnected-(U7E-PI8-PadE4)") (class "Default")
      (node (ref "U7") (pin "E4") (pinfunction "PI8_E4") (pintype "bidirectional"))
    )
  )
)
